# QSFP_uptoQSFP56.net
KiCad netlist of a schematic drawn in Altium Designer
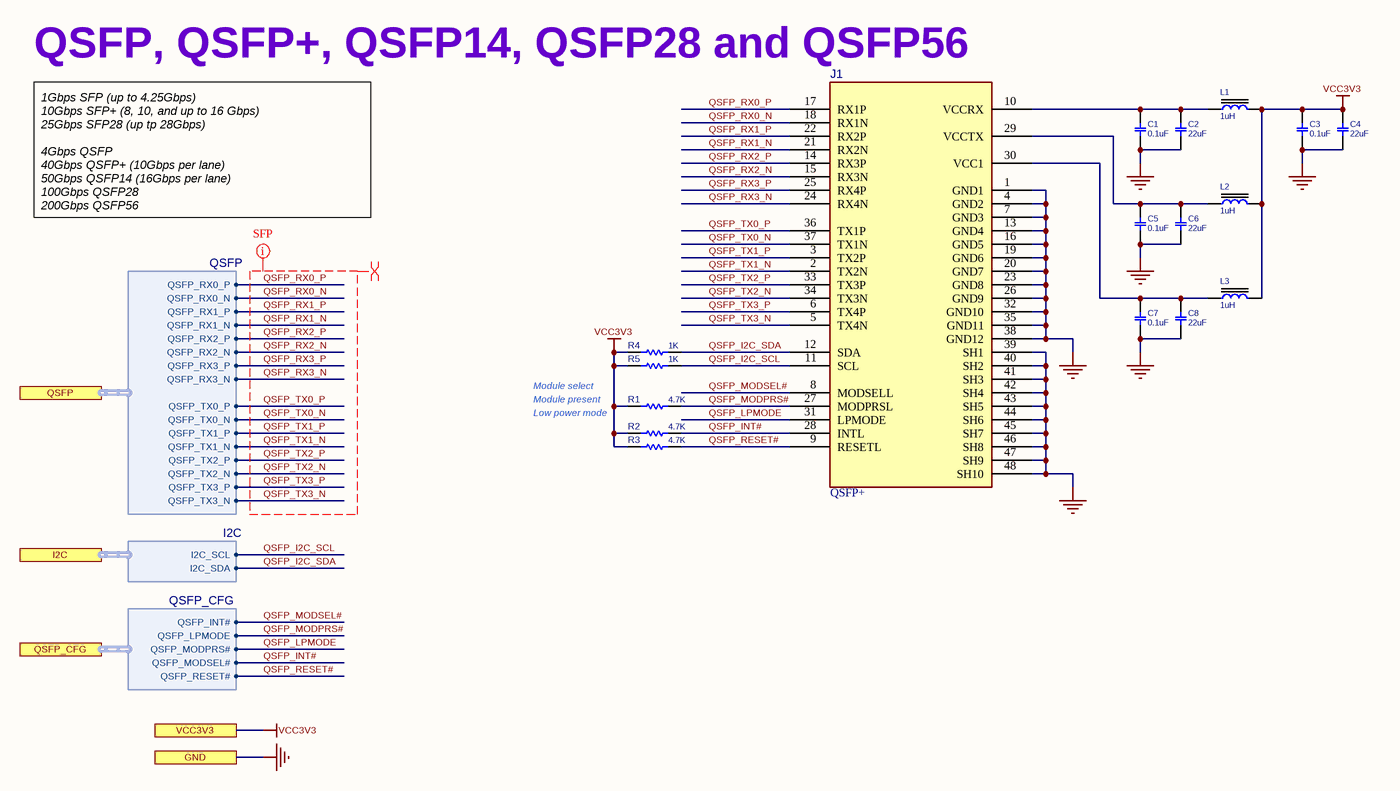
[diagram p0: QSFP_uptoQSFP56.SchDoc]

(export (version "E")
  (design (tool "Eeschema 10.0.6"))
  (components
    (comp (ref "C1")
      (value "0.1uF")
      (footprint "C0402")
      (description "CAP, MLCC, 100nF, 50V, X7R, 10%, 0402C")
      (fields (field (name "MANF") "Taiyo Yuden") (field (name "MANF_P#") "UMK105B7104KVHF"))
      (libsource (lib "mlcc_smd_passive") (part "CAP_SMD_MLCC_100n50T"))
    )
    (comp (ref "C2")
      (value "22uF")
      (footprint "C0603")
      (description "CAP, MLCC, X5R 22uF 20% 25V")
      (fields (field (name "MANF_P#") "JMK325BJ107MM-T") (field (name "MANF") "Taiyo Yuden"))
      (libsource (lib "mlcc_smd_passive") (part "CAP_SMD_MLCC_100u6.3VT"))
    )
    (comp (ref "C3")
      (value "0.1uF")
      (footprint "C0402")
      (description "CAP, MLCC, 100nF, 50V, X7R, 10%, 0402C")
      (fields (field (name "MANF") "Taiyo Yuden") (field (name "MANF_P#") "UMK105B7104KVHF"))
      (libsource (lib "mlcc_smd_passive") (part "CAP_SMD_MLCC_100n50T"))
    )
    (comp (ref "C4")
      (value "22uF")
      (footprint "C0603")
      (description "CAP, MLCC, X5R 22uF 20% 25V")
      (fields (field (name "MANF_P#") "JMK325BJ107MM-T") (field (name "MANF") "Taiyo Yuden"))
      (libsource (lib "mlcc_smd_passive") (part "CAP_SMD_MLCC_100u6.3VT"))
    )
    (comp (ref "C5")
      (value "0.1uF")
      (footprint "C0402")
      (description "CAP, MLCC, 100nF, 50V, X7R, 10%, 0402C")
      (fields (field (name "MANF") "Taiyo Yuden") (field (name "MANF_P#") "UMK105B7104KVHF"))
      (libsource (lib "mlcc_smd_passive") (part "CAP_SMD_MLCC_100n50T"))
    )
    (comp (ref "C6")
      (value "22uF")
      (footprint "C0603")
      (description "CAP, MLCC, X5R 22uF 20% 25V")
      (fields (field (name "MANF_P#") "JMK325BJ107MM-T") (field (name "MANF") "Taiyo Yuden"))
      (libsource (lib "mlcc_smd_passive") (part "CAP_SMD_MLCC_100u6.3VT"))
    )
    (comp (ref "C7")
      (value "0.1uF")
      (footprint "C0402")
      (description "CAP, MLCC, 100nF, 50V, X7R, 10%, 0402C")
      (fields (field (name "MANF") "Taiyo Yuden") (field (name "MANF_P#") "UMK105B7104KVHF"))
      (libsource (lib "mlcc_smd_passive") (part "CAP_SMD_MLCC_100n50T"))
    )
    (comp (ref "C8")
      (value "22uF")
      (footprint "C0603")
      (description "CAP, MLCC, X5R 22uF 20% 25V")
      (fields (field (name "MANF_P#") "JMK325BJ107MM-T") (field (name "MANF") "Taiyo Yuden"))
      (libsource (lib "mlcc_smd_passive") (part "CAP_SMD_MLCC_100u6.3VT"))
    )
    (comp (ref "J1")
      (value "QSFP+")
      (footprint "QSFP28_38_SH")
      (description "CONN, QSFP PLUS (SFP+) RCPT 20POS R/A GOLD SMD")
      (fields (field (name "MANF") "Samtec") (field (name "MANF_P#") "QSFPK-PF-01"))
      (libsource (lib "conn_optic") (part "CONN_QSFP_38_SH"))
    )
    (comp (ref "L1")
      (value "1uH")
      (footprint "L0806")
      (description "INDUCTOR")
      (fields (field (name "MANF_P#") "DFE201610E-1R0M") (field (name "MANF") "Murata"))
      (libsource (lib "inductor_power") (part "IND_SMD_2.2uH_2.9A"))
    )
    (comp (ref "L2")
      (value "1uH")
      (footprint "L0806")
      (description "INDUCTOR")
      (fields (field (name "MANF_P#") "DFE201610E-1R0M") (field (name "MANF") "Murata"))
      (libsource (lib "inductor_power") (part "IND_SMD_2.2uH_2.9A"))
    )
    (comp (ref "L3")
      (value "1uH")
      (footprint "L0806")
      (description "INDUCTOR")
      (fields (field (name "MANF_P#") "DFE201610E-1R0M") (field (name "MANF") "Murata"))
      (libsource (lib "inductor_power") (part "IND_SMD_2.2uH_2.9A"))
    )
    (comp (ref "R1")
      (value "4.7K")
      (footprint "R0402")
      (description "RESISTOR, SMD")
      (fields (field (name "MANF") "Yageo") (field (name "MANF_P#") "RC0402FR-074K7L"))
      (libsource (lib "passive_res_smd") (part "RES_SMD_10K_0402"))
    )
    (comp (ref "R2")
      (value "4.7K")
      (footprint "R0402")
      (description "RESISTOR, SMD")
      (fields (field (name "MANF") "Yageo") (field (name "MANF_P#") "RC0402FR-074K7L"))
      (libsource (lib "passive_res_smd") (part "RES_SMD_10K_0402"))
    )
    (comp (ref "R3")
      (value "4.7K")
      (footprint "R0402")
      (description "RESISTOR, SMD")
      (fields (field (name "MANF") "Yageo") (field (name "MANF_P#") "RC0402FR-074K7L"))
      (libsource (lib "passive_res_smd") (part "RES_SMD_10K_0402"))
    )
    (comp (ref "R4")
      (value "1K")
      (footprint "R0402")
      (description "RESISTOR, SMD")
      (fields (field (name "MANF_P#") "RK73Z1ETTP") (field (name "MANF") "KOA SPEER"))
      (libsource (lib "res_smd_KoaSpeer0402") (part "RES_SMD_0_0402"))
    )
    (comp (ref "R5")
      (value "1K")
      (footprint "R0402")
      (description "RESISTOR, SMD")
      (fields (field (name "MANF_P#") "RK73Z1ETTP") (field (name "MANF") "KOA SPEER"))
      (libsource (lib "res_smd_KoaSpeer0402") (part "RES_SMD_0_0402"))
    )
  )
  (nets
    (net (code "4") (name "/QSFP_I2C_SCL") (class "Default")
      (node (ref "J1") (pin "11") (pinfunction "SCL_11") (pintype "passive"))
      (node (ref "R5") (pin "2") (pinfunction "2_2") (pintype "passive"))
    )
    (net (code "5") (name "/QSFP_I2C_SDA") (class "Default")
      (node (ref "J1") (pin "12") (pinfunction "SDA_12") (pintype "passive"))
      (node (ref "R4") (pin "2") (pinfunction "2_2") (pintype "passive"))
    )
    (net (code "6") (name "/QSFP_INT#") (class "Default")
      (node (ref "J1") (pin "28") (pinfunction "INTL_28") (pintype "passive"))
      (node (ref "R2") (pin "1") (pinfunction "1_1") (pintype "passive"))
    )
    (net (code "7") (name "/QSFP_LPMODE") (class "Default")
      (node (ref "J1") (pin "31") (pinfunction "LPMODE_31") (pintype "passive"))
    )
    (net (code "8") (name "/QSFP_MODPRS#") (class "Default")
      (node (ref "J1") (pin "27") (pinfunction "MODPRSL_27") (pintype "passive"))
      (node (ref "R1") (pin "1") (pinfunction "1_1") (pintype "passive"))
    )
    (net (code "9") (name "/QSFP_MODSEL#") (class "Default")
      (node (ref "J1") (pin "8") (pinfunction "MODSELL_8") (pintype "passive"))
    )
    (net (code "10") (name "/QSFP_RESET#") (class "Default")
      (node (ref "J1") (pin "9") (pinfunction "RESETL_9") (pintype "passive"))
      (node (ref "R3") (pin "1") (pinfunction "1_1") (pintype "passive"))
    )
    (net (code "11") (name "/QSFP_RX0_N") (class "Default")
      (node (ref "J1") (pin "18") (pinfunction "RX1N_18") (pintype "passive"))
    )
    (net (code "12") (name "/QSFP_RX0_P") (class "Default")
      (node (ref "J1") (pin "17") (pinfunction "RX1P_17") (pintype "passive"))
    )
    (net (code "13") (name "/QSFP_RX1_N") (class "Default")
      (node (ref "J1") (pin "21") (pinfunction "RX2N_21") (pintype "passive"))
    )
    (net (code "14") (name "/QSFP_RX1_P") (class "Default")
      (node (ref "J1") (pin "22") (pinfunction "RX2P_22") (pintype "passive"))
    )
    (net (code "15") (name "/QSFP_RX2_N") (class "Default")
      (node (ref "J1") (pin "15") (pinfunction "RX3N_15") (pintype "passive"))
    )
    (net (code "16") (name "/QSFP_RX2_P") (class "Default")
      (node (ref "J1") (pin "14") (pinfunction "RX3P_14") (pintype "passive"))
    )
    (net (code "17") (name "/QSFP_RX3_N") (class "Default")
      (node (ref "J1") (pin "24") (pinfunction "RX4N_24") (pintype "passive"))
    )
    (net (code "18") (name "/QSFP_RX3_P") (class "Default")
      (node (ref "J1") (pin "25") (pinfunction "RX4P_25") (pintype "passive"))
    )
    (net (code "19") (name "/QSFP_TX0_N") (class "Default")
      (node (ref "J1") (pin "37") (pinfunction "TX1N_37") (pintype "passive"))
    )
    (net (code "20") (name "/QSFP_TX0_P") (class "Default")
      (node (ref "J1") (pin "36") (pinfunction "TX1P_36") (pintype "passive"))
    )
    (net (code "21") (name "/QSFP_TX1_N") (class "Default")
      (node (ref "J1") (pin "2") (pinfunction "TX2N_2") (pintype "passive"))
    )
    (net (code "22") (name "/QSFP_TX1_P") (class "Default")
      (node (ref "J1") (pin "3") (pinfunction "TX2P_3") (pintype "passive"))
    )
    (net (code "23") (name "/QSFP_TX2_N") (class "Default")
      (node (ref "J1") (pin "34") (pinfunction "TX3N_34") (pintype "passive"))
    )
    (net (code "24") (name "/QSFP_TX2_P") (class "Default")
      (node (ref "J1") (pin "33") (pinfunction "TX3P_33") (pintype "passive"))
    )
    (net (code "25") (name "/QSFP_TX3_N") (class "Default")
      (node (ref "J1") (pin "5") (pinfunction "TX4N_5") (pintype "passive"))
    )
    (net (code "26") (name "/QSFP_TX3_P") (class "Default")
      (node (ref "J1") (pin "6") (pinfunction "TX4P_6") (pintype "passive"))
    )
    (net (code "30") (name "GND") (class "Default")
      (node (ref "C1") (pin "2") (pinfunction "2_2") (pintype "passive"))
      (node (ref "C2") (pin "2") (pinfunction "2_2") (pintype "passive"))
      (node (ref "C3") (pin "1") (pinfunction "1_1") (pintype "passive"))
      (node (ref "C4") (pin "2") (pinfunction "2_2") (pintype "passive"))
      (node (ref "C5") (pin "1") (pinfunction "1_1") (pintype "passive"))
      (node (ref "C6") (pin "2") (pinfunction "2_2") (pintype "passive"))
      (node (ref "C7") (pin "1") (pinfunction "1_1") (pintype "passive"))
      (node (ref "C8") (pin "2") (pinfunction "2_2") (pintype "passive"))
      (node (ref "J1") (pin "1") (pinfunction "GND1_1") (pintype "passive"))
      (node (ref "J1") (pin "13") (pinfunction "GND4_13") (pintype "passive"))
      (node (ref "J1") (pin "16") (pinfunction "GND5_16") (pintype "passive"))
      (node (ref "J1") (pin "19") (pinfunction "GND6_19") (pintype "passive"))
      (node (ref "J1") (pin "20") (pinfunction "GND7_20") (pintype "passive"))
      (node (ref "J1") (pin "23") (pinfunction "GND8_23") (pintype "passive"))
      (node (ref "J1") (pin "26") (pinfunction "GND9_26") (pintype "passive"))
      (node (ref "J1") (pin "32") (pinfunction "GND10_32") (pintype "passive"))
      (node (ref "J1") (pin "35") (pinfunction "GND11_35") (pintype "passive"))
      (node (ref "J1") (pin "38") (pinfunction "GND12_38") (pintype "passive"))
      (node (ref "J1") (pin "39") (pinfunction "SH1_39") (pintype "passive"))
      (node (ref "J1") (pin "4") (pinfunction "GND2_4") (pintype "passive"))
      (node (ref "J1") (pin "40") (pinfunction "SH2_40") (pintype "passive"))
      (node (ref "J1") (pin "41") (pinfunction "SH3_41") (pintype "passive"))
      (node (ref "J1") (pin "42") (pinfunction "SH4_42") (pintype "passive"))
      (node (ref "J1") (pin "43") (pinfunction "SH5_43") (pintype "passive"))
      (node (ref "J1") (pin "44") (pinfunction "SH6_44") (pintype "passive"))
      (node (ref "J1") (pin "45") (pinfunction "SH7_45") (pintype "passive"))
      (node (ref "J1") (pin "46") (pinfunction "SH8_46") (pintype "passive"))
      (node (ref "J1") (pin "47") (pinfunction "SH9_47") (pintype "passive"))
      (node (ref "J1") (pin "48") (pinfunction "SH10_48") (pintype "passive"))
      (node (ref "J1") (pin "7") (pinfunction "GND3_7") (pintype "passive"))
    )
    (net (code "31") (name "Net-(J1-VCC1)") (class "Default")
      (node (ref "C7") (pin "2") (pinfunction "2_2") (pintype "passive"))
      (node (ref "C8") (pin "1") (pinfunction "1_1") (pintype "passive"))
      (node (ref "J1") (pin "30") (pinfunction "VCC1_30") (pintype "passive"))
      (node (ref "L3") (pin "1") (pinfunction "1_1") (pintype "passive"))
    )
    (net (code "32") (name "Net-(J1-VCCRX)") (class "Default")
      (node (ref "C1") (pin "1") (pinfunction "1_1") (pintype "passive"))
      (node (ref "C2") (pin "1") (pinfunction "1_1") (pintype "passive"))
      (node (ref "J1") (pin "10") (pinfunction "VCCRX_10") (pintype "passive"))
      (node (ref "L1") (pin "1") (pinfunction "1_1") (pintype "passive"))
    )
    (net (code "33") (name "Net-(J1-VCCTX)") (class "Default")
      (node (ref "C5") (pin "2") (pinfunction "2_2") (pintype "passive"))
      (node (ref "C6") (pin "1") (pinfunction "1_1") (pintype "passive"))
      (node (ref "J1") (pin "29") (pinfunction "VCCTX_29") (pintype "passive"))
      (node (ref "L2") (pin "1") (pinfunction "1_1") (pintype "passive"))
    )
    (net (code "34") (name "VCC3V3") (class "Default")
      (node (ref "C3") (pin "2") (pinfunction "2_2") (pintype "passive"))
      (node (ref "C4") (pin "1") (pinfunction "1_1") (pintype "passive"))
      (node (ref "L1") (pin "2") (pinfunction "2_2") (pintype "passive"))
      (node (ref "L2") (pin "2") (pinfunction "2_2") (pintype "passive"))
      (node (ref "L3") (pin "2") (pinfunction "2_2") (pintype "passive"))
      (node (ref "R1") (pin "2") (pinfunction "2_2") (pintype "passive"))
      (node (ref "R2") (pin "2") (pinfunction "2_2") (pintype "passive"))
      (node (ref "R3") (pin "2") (pinfunction "2_2") (pintype "passive"))
      (node (ref "R4") (pin "1") (pinfunction "1_1") (pintype "passive"))
      (node (ref "R5") (pin "1") (pinfunction "1_1") (pintype "passive"))
    )
  )
)
